# midi_schem.net
KiCad netlist of a schematic drawn in EAGLE
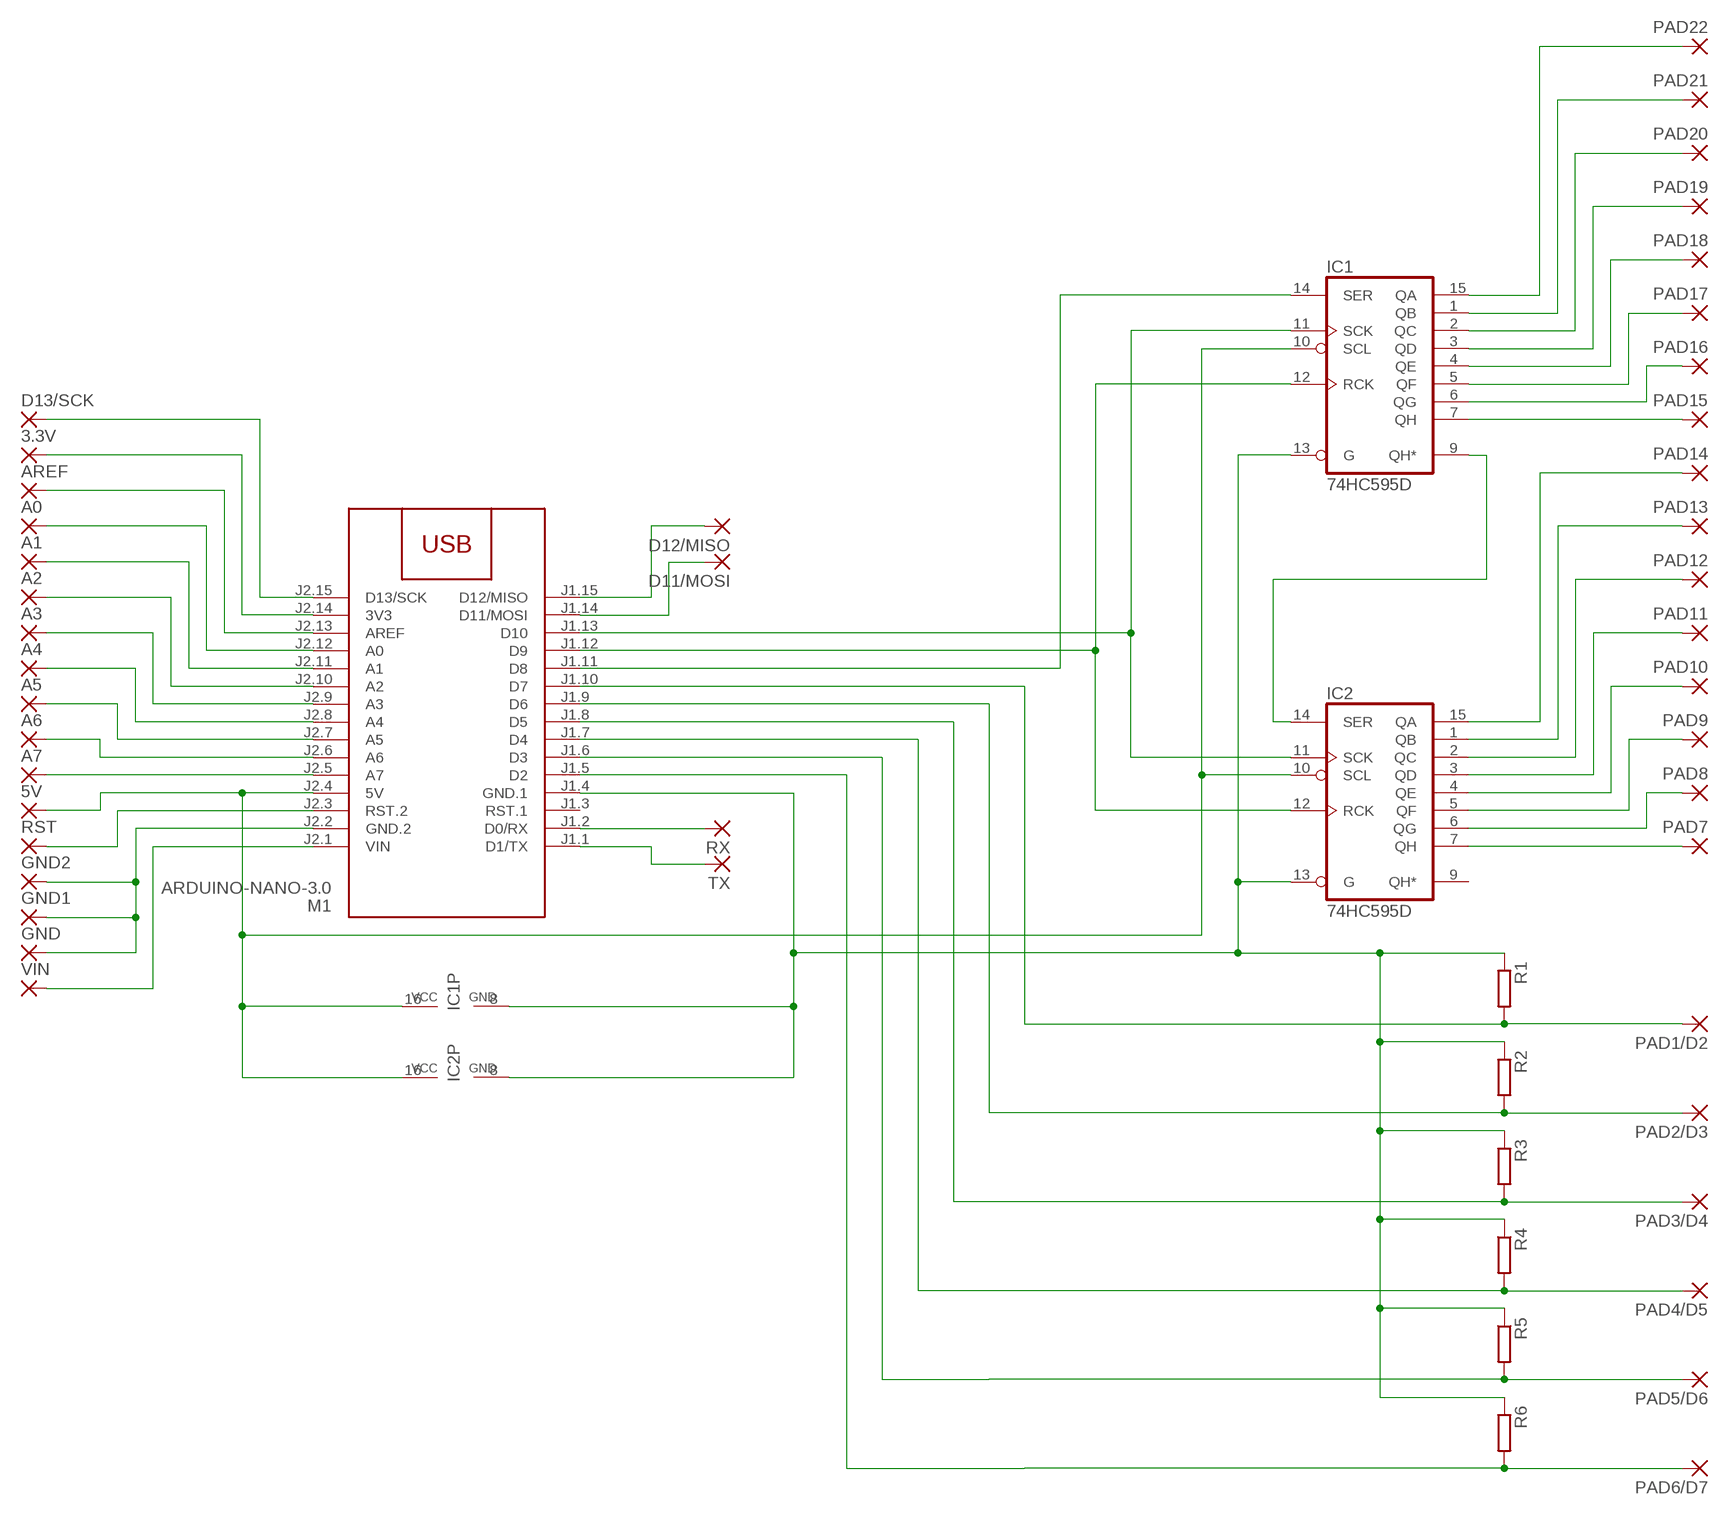
[diagram p0: schematic, sheet 1]

(export (version "E")
  (design (tool "Eeschema 10.0.6"))
  (components
    (comp (ref "3.3V")
      (value "2,54/0,8")
      (footprint "eagle-import:2,54_0,8")
      (libsource (lib "eagle-import") (part "2,54/0,8"))
    )
    (comp (ref "5V")
      (value "2,54/0,8")
      (footprint "eagle-import:2,54_0,8")
      (libsource (lib "eagle-import") (part "2,54/0,8"))
    )
    (comp (ref "A0")
      (value "2,54/0,8")
      (footprint "eagle-import:2,54_0,8")
      (libsource (lib "eagle-import") (part "2,54/0,8"))
    )
    (comp (ref "A1")
      (value "2,54/0,8")
      (footprint "eagle-import:2,54_0,8")
      (libsource (lib "eagle-import") (part "2,54/0,8"))
    )
    (comp (ref "A2")
      (value "2,54/0,8")
      (footprint "eagle-import:2,54_0,8")
      (libsource (lib "eagle-import") (part "2,54/0,8"))
    )
    (comp (ref "A3")
      (value "2,54/0,8")
      (footprint "eagle-import:2,54_0,8")
      (libsource (lib "eagle-import") (part "2,54/0,8"))
    )
    (comp (ref "A4")
      (value "2,54/0,8")
      (footprint "eagle-import:2,54_0,8")
      (libsource (lib "eagle-import") (part "2,54/0,8"))
    )
    (comp (ref "A5")
      (value "2,54/0,8")
      (footprint "eagle-import:2,54_0,8")
      (libsource (lib "eagle-import") (part "2,54/0,8"))
    )
    (comp (ref "A6")
      (value "2,54/0,8")
      (footprint "eagle-import:2,54_0,8")
      (libsource (lib "eagle-import") (part "2,54/0,8"))
    )
    (comp (ref "A7")
      (value "2,54/0,8")
      (footprint "eagle-import:2,54_0,8")
      (libsource (lib "eagle-import") (part "2,54/0,8"))
    )
    (comp (ref "AREF")
      (value "2,54/0,8")
      (footprint "eagle-import:2,54_0,8")
      (libsource (lib "eagle-import") (part "2,54/0,8"))
    )
    (comp (ref "D11/MOSI")
      (value "2,54/0,8")
      (footprint "eagle-import:2,54_0,8")
      (libsource (lib "eagle-import") (part "2,54/0,8"))
    )
    (comp (ref "D12/MISO")
      (value "2,54/0,8")
      (footprint "eagle-import:2,54_0,8")
      (libsource (lib "eagle-import") (part "2,54/0,8"))
    )
    (comp (ref "D13/SCK")
      (value "2,54/0,8")
      (footprint "eagle-import:2,54_0,8")
      (libsource (lib "eagle-import") (part "2,54/0,8"))
    )
    (comp (ref "GND")
      (value "2,54/0,8")
      (footprint "eagle-import:2,54_0,8")
      (libsource (lib "eagle-import") (part "2,54/0,8"))
    )
    (comp (ref "GND1")
      (value "2,54/0,8")
      (footprint "eagle-import:2,54_0,8")
      (libsource (lib "eagle-import") (part "2,54/0,8"))
    )
    (comp (ref "GND2")
      (value "2,54/0,8")
      (footprint "eagle-import:2,54_0,8")
      (libsource (lib "eagle-import") (part "2,54/0,8"))
    )
    (comp (ref "IC1")
      (value "74HC595D")
      (footprint "eagle-import:SO16")
      (libsource (lib "eagle-import") (part "74595DHC"))
    )
    (comp (ref "IC2")
      (value "74HC595D")
      (footprint "eagle-import:SO16")
      (libsource (lib "eagle-import") (part "74595DHC"))
    )
    (comp (ref "M1")
      (value "ARDUINO-NANO-3.0")
      (footprint "eagle-import:ARDUINO-NANO-3.0")
      (libsource (lib "eagle-import") (part "ARDUINO-NANO-3.0"))
    )
    (comp (ref "PAD1/D2")
      (value "SMD2")
      (footprint "eagle-import:SMD1,27-2,54")
      (libsource (lib "eagle-import") (part "SMD2"))
    )
    (comp (ref "PAD2/D3")
      (value "SMD2")
      (footprint "eagle-import:SMD1,27-2,54")
      (libsource (lib "eagle-import") (part "SMD2"))
    )
    (comp (ref "PAD3/D4")
      (value "SMD2")
      (footprint "eagle-import:SMD1,27-2,54")
      (libsource (lib "eagle-import") (part "SMD2"))
    )
    (comp (ref "PAD4/D5")
      (value "SMD2")
      (footprint "eagle-import:SMD1,27-2,54")
      (libsource (lib "eagle-import") (part "SMD2"))
    )
    (comp (ref "PAD5/D6")
      (value "SMD2")
      (footprint "eagle-import:SMD1,27-2,54")
      (libsource (lib "eagle-import") (part "SMD2"))
    )
    (comp (ref "PAD6/D7")
      (value "SMD2")
      (footprint "eagle-import:SMD1,27-2,54")
      (libsource (lib "eagle-import") (part "SMD2"))
    )
    (comp (ref "PAD7")
      (value "SMD2")
      (footprint "eagle-import:SMD1,27-2,54")
      (libsource (lib "eagle-import") (part "SMD2"))
    )
    (comp (ref "PAD8")
      (value "SMD2")
      (footprint "eagle-import:SMD1,27-2,54")
      (libsource (lib "eagle-import") (part "SMD2"))
    )
    (comp (ref "PAD9")
      (value "SMD2")
      (footprint "eagle-import:SMD1,27-2,54")
      (libsource (lib "eagle-import") (part "SMD2"))
    )
    (comp (ref "PAD10")
      (value "SMD2")
      (footprint "eagle-import:SMD1,27-2,54")
      (libsource (lib "eagle-import") (part "SMD2"))
    )
    (comp (ref "PAD11")
      (value "SMD2")
      (footprint "eagle-import:SMD1,27-2,54")
      (libsource (lib "eagle-import") (part "SMD2"))
    )
    (comp (ref "PAD12")
      (value "SMD2")
      (footprint "eagle-import:SMD1,27-2,54")
      (libsource (lib "eagle-import") (part "SMD2"))
    )
    (comp (ref "PAD13")
      (value "SMD2")
      (footprint "eagle-import:SMD1,27-2,54")
      (libsource (lib "eagle-import") (part "SMD2"))
    )
    (comp (ref "PAD14")
      (value "SMD2")
      (footprint "eagle-import:SMD1,27-2,54")
      (libsource (lib "eagle-import") (part "SMD2"))
    )
    (comp (ref "PAD15")
      (value "SMD2")
      (footprint "eagle-import:SMD1,27-2,54")
      (libsource (lib "eagle-import") (part "SMD2"))
    )
    (comp (ref "PAD16")
      (value "SMD2")
      (footprint "eagle-import:SMD1,27-2,54")
      (libsource (lib "eagle-import") (part "SMD2"))
    )
    (comp (ref "PAD17")
      (value "SMD2")
      (footprint "eagle-import:SMD1,27-2,54")
      (libsource (lib "eagle-import") (part "SMD2"))
    )
    (comp (ref "PAD18")
      (value "SMD2")
      (footprint "eagle-import:SMD1,27-2,54")
      (libsource (lib "eagle-import") (part "SMD2"))
    )
    (comp (ref "PAD19")
      (value "SMD2")
      (footprint "eagle-import:SMD1,27-2,54")
      (libsource (lib "eagle-import") (part "SMD2"))
    )
    (comp (ref "PAD20")
      (value "SMD2")
      (footprint "eagle-import:SMD1,27-2,54")
      (libsource (lib "eagle-import") (part "SMD2"))
    )
    (comp (ref "PAD21")
      (value "SMD2")
      (footprint "eagle-import:SMD1,27-2,54")
      (libsource (lib "eagle-import") (part "SMD2"))
    )
    (comp (ref "PAD22")
      (value "SMD2")
      (footprint "eagle-import:SMD1,27-2,54")
      (libsource (lib "eagle-import") (part "SMD2"))
    )
    (comp (ref "R1")
      (value "R-EU_0207/10")
      (footprint "eagle-import:0207_10")
      (libsource (lib "eagle-import") (part "R-EU_0207/10"))
    )
    (comp (ref "R2")
      (value "R-EU_0207/10")
      (footprint "eagle-import:0207_10")
      (libsource (lib "eagle-import") (part "R-EU_0207/10"))
    )
    (comp (ref "R3")
      (value "R-EU_0207/10")
      (footprint "eagle-import:0207_10")
      (libsource (lib "eagle-import") (part "R-EU_0207/10"))
    )
    (comp (ref "R4")
      (value "R-EU_0207/10")
      (footprint "eagle-import:0207_10")
      (libsource (lib "eagle-import") (part "R-EU_0207/10"))
    )
    (comp (ref "R5")
      (value "R-EU_0207/10")
      (footprint "eagle-import:0207_10")
      (libsource (lib "eagle-import") (part "R-EU_0207/10"))
    )
    (comp (ref "R6")
      (value "R-EU_0207/10")
      (footprint "eagle-import:0207_10")
      (libsource (lib "eagle-import") (part "R-EU_0207/10"))
    )
    (comp (ref "RST")
      (value "2,54/0,8")
      (footprint "eagle-import:2,54_0,8")
      (libsource (lib "eagle-import") (part "2,54/0,8"))
    )
    (comp (ref "RX")
      (value "2,54/0,8")
      (footprint "eagle-import:2,54_0,8")
      (libsource (lib "eagle-import") (part "2,54/0,8"))
    )
    (comp (ref "TX")
      (value "2,54/0,8")
      (footprint "eagle-import:2,54_0,8")
      (libsource (lib "eagle-import") (part "2,54/0,8"))
    )
    (comp (ref "VIN")
      (value "2,54/0,8")
      (footprint "eagle-import:2,54_0,8")
      (libsource (lib "eagle-import") (part "2,54/0,8"))
    )
  )
  (nets
    (net (code "1") (name "Net-(3.3V-P)") (class "Default")
      (node (ref "3.3V") (pin "1") (pinfunction "P_1") (pintype "passive"))
      (node (ref "M1") (pin "J2.14") (pinfunction "3V3_J2.14") (pintype "power_in"))
    )
    (net (code "2") (name "Net-(5V-P)") (class "Default")
      (node (ref "5V") (pin "1") (pinfunction "P_1") (pintype "passive"))
      (node (ref "IC1") (pin "10") (pinfunction "SCL_10") (pintype "input"))
      (node (ref "IC1") (pin "16") (pinfunction "VCC_16") (pintype "power_in"))
      (node (ref "IC2") (pin "10") (pinfunction "SCL_10") (pintype "input"))
      (node (ref "IC2") (pin "16") (pinfunction "VCC_16") (pintype "power_in"))
      (node (ref "M1") (pin "J2.4") (pinfunction "5V_J2.4") (pintype "power_in"))
    )
    (net (code "3") (name "Net-(A0-P)") (class "Default")
      (node (ref "A0") (pin "1") (pinfunction "P_1") (pintype "passive"))
      (node (ref "M1") (pin "J2.12") (pinfunction "A0_J2.12") (pintype "bidirectional"))
    )
    (net (code "4") (name "Net-(A1-P)") (class "Default")
      (node (ref "A1") (pin "1") (pinfunction "P_1") (pintype "passive"))
      (node (ref "M1") (pin "J2.11") (pinfunction "A1_J2.11") (pintype "bidirectional"))
    )
    (net (code "5") (name "Net-(A2-P)") (class "Default")
      (node (ref "A2") (pin "1") (pinfunction "P_1") (pintype "passive"))
      (node (ref "M1") (pin "J2.10") (pinfunction "A2_J2.10") (pintype "bidirectional"))
    )
    (net (code "6") (name "Net-(A3-P)") (class "Default")
      (node (ref "A3") (pin "1") (pinfunction "P_1") (pintype "passive"))
      (node (ref "M1") (pin "J2.9") (pinfunction "A3_J2.9") (pintype "bidirectional"))
    )
    (net (code "7") (name "Net-(A4-P)") (class "Default")
      (node (ref "A4") (pin "1") (pinfunction "P_1") (pintype "passive"))
      (node (ref "M1") (pin "J2.8") (pinfunction "A4_J2.8") (pintype "bidirectional"))
    )
    (net (code "8") (name "Net-(A5-P)") (class "Default")
      (node (ref "A5") (pin "1") (pinfunction "P_1") (pintype "passive"))
      (node (ref "M1") (pin "J2.7") (pinfunction "A5_J2.7") (pintype "bidirectional"))
    )
    (net (code "9") (name "Net-(A6-P)") (class "Default")
      (node (ref "A6") (pin "1") (pinfunction "P_1") (pintype "passive"))
      (node (ref "M1") (pin "J2.6") (pinfunction "A6_J2.6") (pintype "bidirectional"))
    )
    (net (code "10") (name "Net-(A7-P)") (class "Default")
      (node (ref "A7") (pin "1") (pinfunction "P_1") (pintype "passive"))
      (node (ref "M1") (pin "J2.5") (pinfunction "A7_J2.5") (pintype "bidirectional"))
    )
    (net (code "11") (name "Net-(AREF-P)") (class "Default")
      (node (ref "AREF") (pin "1") (pinfunction "P_1") (pintype "passive"))
      (node (ref "M1") (pin "J2.13") (pinfunction "AREF_J2.13") (pintype "bidirectional"))
    )
    (net (code "12") (name "Net-(D11/MOSI-P)") (class "Default")
      (node (ref "D11/MOSI") (pin "1") (pinfunction "P_1") (pintype "passive"))
      (node (ref "M1") (pin "J1.14") (pinfunction "D11/MOSI_J1.14") (pintype "bidirectional"))
    )
    (net (code "13") (name "Net-(D12/MISO-P)") (class "Default")
      (node (ref "D12/MISO") (pin "1") (pinfunction "P_1") (pintype "passive"))
      (node (ref "M1") (pin "J1.15") (pinfunction "D12/MISO_J1.15") (pintype "bidirectional"))
    )
    (net (code "14") (name "Net-(D13/SCK-P)") (class "Default")
      (node (ref "D13/SCK") (pin "1") (pinfunction "P_1") (pintype "passive"))
      (node (ref "M1") (pin "J2.15") (pinfunction "D13/SCK_J2.15") (pintype "bidirectional"))
    )
    (net (code "15") (name "Net-(GND-P)") (class "Default")
      (node (ref "GND") (pin "1") (pinfunction "P_1") (pintype "passive"))
      (node (ref "GND1") (pin "1") (pinfunction "P_1") (pintype "passive"))
      (node (ref "GND2") (pin "1") (pinfunction "P_1") (pintype "passive"))
      (node (ref "M1") (pin "J2.2") (pinfunction "GND.2_J2.2") (pintype "power_in"))
    )
    (net (code "16") (name "Net-(IC1A-G)") (class "Default")
      (node (ref "IC1") (pin "13") (pinfunction "G_13") (pintype "input"))
      (node (ref "IC1") (pin "8") (pinfunction "GND_8") (pintype "power_in"))
      (node (ref "IC2") (pin "13") (pinfunction "G_13") (pintype "input"))
      (node (ref "IC2") (pin "8") (pinfunction "GND_8") (pintype "power_in"))
      (node (ref "M1") (pin "J1.4") (pinfunction "GND.1_J1.4") (pintype "power_in"))
      (node (ref "R1") (pin "1") (pinfunction "1_1") (pintype "passive"))
      (node (ref "R2") (pin "1") (pinfunction "1_1") (pintype "passive"))
      (node (ref "R3") (pin "1") (pinfunction "1_1") (pintype "passive"))
      (node (ref "R4") (pin "1") (pinfunction "1_1") (pintype "passive"))
      (node (ref "R5") (pin "1") (pinfunction "1_1") (pintype "passive"))
      (node (ref "R6") (pin "1") (pinfunction "1_1") (pintype "passive"))
    )
    (net (code "17") (name "Net-(IC1A-QA)") (class "Default")
      (node (ref "IC1") (pin "15") (pinfunction "QA_15") (pintype "tri_state"))
      (node (ref "PAD22") (pin "1") (pinfunction "P_1") (pintype "passive"))
    )
    (net (code "18") (name "Net-(IC1A-QB)") (class "Default")
      (node (ref "IC1") (pin "1") (pinfunction "QB_1") (pintype "tri_state"))
      (node (ref "PAD21") (pin "1") (pinfunction "P_1") (pintype "passive"))
    )
    (net (code "19") (name "Net-(IC1A-QC)") (class "Default")
      (node (ref "IC1") (pin "2") (pinfunction "QC_2") (pintype "tri_state"))
      (node (ref "PAD20") (pin "1") (pinfunction "P_1") (pintype "passive"))
    )
    (net (code "20") (name "Net-(IC1A-QD)") (class "Default")
      (node (ref "IC1") (pin "3") (pinfunction "QD_3") (pintype "tri_state"))
      (node (ref "PAD19") (pin "1") (pinfunction "P_1") (pintype "passive"))
    )
    (net (code "21") (name "Net-(IC1A-QE)") (class "Default")
      (node (ref "IC1") (pin "4") (pinfunction "QE_4") (pintype "tri_state"))
      (node (ref "PAD18") (pin "1") (pinfunction "P_1") (pintype "passive"))
    )
    (net (code "22") (name "Net-(IC1A-QF)") (class "Default")
      (node (ref "IC1") (pin "5") (pinfunction "QF_5") (pintype "tri_state"))
      (node (ref "PAD17") (pin "1") (pinfunction "P_1") (pintype "passive"))
    )
    (net (code "23") (name "Net-(IC1A-QG)") (class "Default")
      (node (ref "IC1") (pin "6") (pinfunction "QG_6") (pintype "tri_state"))
      (node (ref "PAD16") (pin "1") (pinfunction "P_1") (pintype "passive"))
    )
    (net (code "24") (name "Net-(IC1A-QH)") (class "Default")
      (node (ref "IC1") (pin "7") (pinfunction "QH_7") (pintype "tri_state"))
      (node (ref "PAD15") (pin "1") (pinfunction "P_1") (pintype "passive"))
    )
    (net (code "25") (name "Net-(IC1A-QH*)") (class "Default")
      (node (ref "IC1") (pin "9") (pinfunction "QH*_9") (pintype "tri_state"))
      (node (ref "IC2") (pin "14") (pinfunction "SER_14") (pintype "input"))
    )
    (net (code "26") (name "Net-(IC1A-RCK)") (class "Default")
      (node (ref "IC1") (pin "12") (pinfunction "RCK_12") (pintype "input"))
      (node (ref "IC2") (pin "12") (pinfunction "RCK_12") (pintype "input"))
      (node (ref "M1") (pin "J1.12") (pinfunction "D9_J1.12") (pintype "bidirectional"))
    )
    (net (code "27") (name "Net-(IC1A-SCK)") (class "Default")
      (node (ref "IC1") (pin "11") (pinfunction "SCK_11") (pintype "input"))
      (node (ref "IC2") (pin "11") (pinfunction "SCK_11") (pintype "input"))
      (node (ref "M1") (pin "J1.13") (pinfunction "D10_J1.13") (pintype "bidirectional"))
    )
    (net (code "28") (name "Net-(IC1A-SER)") (class "Default")
      (node (ref "IC1") (pin "14") (pinfunction "SER_14") (pintype "input"))
      (node (ref "M1") (pin "J1.11") (pinfunction "D8_J1.11") (pintype "bidirectional"))
    )
    (net (code "29") (name "Net-(IC2A-QA)") (class "Default")
      (node (ref "IC2") (pin "15") (pinfunction "QA_15") (pintype "tri_state"))
      (node (ref "PAD14") (pin "1") (pinfunction "P_1") (pintype "passive"))
    )
    (net (code "30") (name "Net-(IC2A-QB)") (class "Default")
      (node (ref "IC2") (pin "1") (pinfunction "QB_1") (pintype "tri_state"))
      (node (ref "PAD13") (pin "1") (pinfunction "P_1") (pintype "passive"))
    )
    (net (code "31") (name "Net-(IC2A-QC)") (class "Default")
      (node (ref "IC2") (pin "2") (pinfunction "QC_2") (pintype "tri_state"))
      (node (ref "PAD12") (pin "1") (pinfunction "P_1") (pintype "passive"))
    )
    (net (code "32") (name "Net-(IC2A-QD)") (class "Default")
      (node (ref "IC2") (pin "3") (pinfunction "QD_3") (pintype "tri_state"))
      (node (ref "PAD11") (pin "1") (pinfunction "P_1") (pintype "passive"))
    )
    (net (code "33") (name "Net-(IC2A-QE)") (class "Default")
      (node (ref "IC2") (pin "4") (pinfunction "QE_4") (pintype "tri_state"))
      (node (ref "PAD10") (pin "1") (pinfunction "P_1") (pintype "passive"))
    )
    (net (code "34") (name "Net-(IC2A-QF)") (class "Default")
      (node (ref "IC2") (pin "5") (pinfunction "QF_5") (pintype "tri_state"))
      (node (ref "PAD9") (pin "1") (pinfunction "P_1") (pintype "passive"))
    )
    (net (code "35") (name "Net-(IC2A-QG)") (class "Default")
      (node (ref "IC2") (pin "6") (pinfunction "QG_6") (pintype "tri_state"))
      (node (ref "PAD8") (pin "1") (pinfunction "P_1") (pintype "passive"))
    )
    (net (code "36") (name "Net-(IC2A-QH)") (class "Default")
      (node (ref "IC2") (pin "7") (pinfunction "QH_7") (pintype "tri_state"))
      (node (ref "PAD7") (pin "1") (pinfunction "P_1") (pintype "passive"))
    )
    (net (code "37") (name "Net-(M1-D0{slash}RX)") (class "Default")
      (node (ref "M1") (pin "J1.2") (pinfunction "D0/RX_J1.2") (pintype "bidirectional"))
      (node (ref "RX") (pin "1") (pinfunction "P_1") (pintype "passive"))
    )
    (net (code "38") (name "Net-(M1-D1{slash}TX)") (class "Default")
      (node (ref "M1") (pin "J1.1") (pinfunction "D1/TX_J1.1") (pintype "bidirectional"))
      (node (ref "TX") (pin "1") (pinfunction "P_1") (pintype "passive"))
    )
    (net (code "39") (name "Net-(M1-D2)") (class "Default")
      (node (ref "M1") (pin "J1.5") (pinfunction "D2_J1.5") (pintype "bidirectional"))
      (node (ref "PAD6/D7") (pin "1") (pinfunction "P_1") (pintype "passive"))
      (node (ref "R6") (pin "2") (pinfunction "2_2") (pintype "passive"))
    )
    (net (code "40") (name "Net-(M1-D3)") (class "Default")
      (node (ref "M1") (pin "J1.6") (pinfunction "D3_J1.6") (pintype "bidirectional"))
      (node (ref "PAD5/D6") (pin "1") (pinfunction "P_1") (pintype "passive"))
      (node (ref "R5") (pin "2") (pinfunction "2_2") (pintype "passive"))
    )
    (net (code "41") (name "Net-(M1-D4)") (class "Default")
      (node (ref "M1") (pin "J1.7") (pinfunction "D4_J1.7") (pintype "bidirectional"))
      (node (ref "PAD4/D5") (pin "1") (pinfunction "P_1") (pintype "passive"))
      (node (ref "R4") (pin "2") (pinfunction "2_2") (pintype "passive"))
    )
    (net (code "42") (name "Net-(M1-D5)") (class "Default")
      (node (ref "M1") (pin "J1.8") (pinfunction "D5_J1.8") (pintype "bidirectional"))
      (node (ref "PAD3/D4") (pin "1") (pinfunction "P_1") (pintype "passive"))
      (node (ref "R3") (pin "2") (pinfunction "2_2") (pintype "passive"))
    )
    (net (code "43") (name "Net-(M1-D6)") (class "Default")
      (node (ref "M1") (pin "J1.9") (pinfunction "D6_J1.9") (pintype "bidirectional"))
      (node (ref "PAD2/D3") (pin "1") (pinfunction "P_1") (pintype "passive"))
      (node (ref "R2") (pin "2") (pinfunction "2_2") (pintype "passive"))
    )
    (net (code "44") (name "Net-(M1-D7)") (class "Default")
      (node (ref "M1") (pin "J1.10") (pinfunction "D7_J1.10") (pintype "bidirectional"))
      (node (ref "PAD1/D2") (pin "1") (pinfunction "P_1") (pintype "passive"))
      (node (ref "R1") (pin "2") (pinfunction "2_2") (pintype "passive"))
    )
    (net (code "45") (name "Net-(M1-RST.2)") (class "Default")
      (node (ref "M1") (pin "J2.3") (pinfunction "RST.2_J2.3") (pintype "bidirectional"))
      (node (ref "RST") (pin "1") (pinfunction "P_1") (pintype "passive"))
    )
    (net (code "46") (name "Net-(M1-VIN)") (class "Default")
      (node (ref "M1") (pin "J2.1") (pinfunction "VIN_J2.1") (pintype "power_in"))
      (node (ref "VIN") (pin "1") (pinfunction "P_1") (pintype "passive"))
    )
    (net (code "47") (name "unconnected-(IC2A-QH*-Pad9)") (class "Default")
      (node (ref "IC2") (pin "9") (pinfunction "QH*_9") (pintype "tri_state"))
    )
    (net (code "48") (name "unconnected-(M1-RST.1-PadJ1.3)") (class "Default")
      (node (ref "M1") (pin "J1.3") (pinfunction "RST.1_J1.3") (pintype "bidirectional"))
    )
  )
)
